# power.net
KiCad netlist of a schematic drawn in Altium Designer
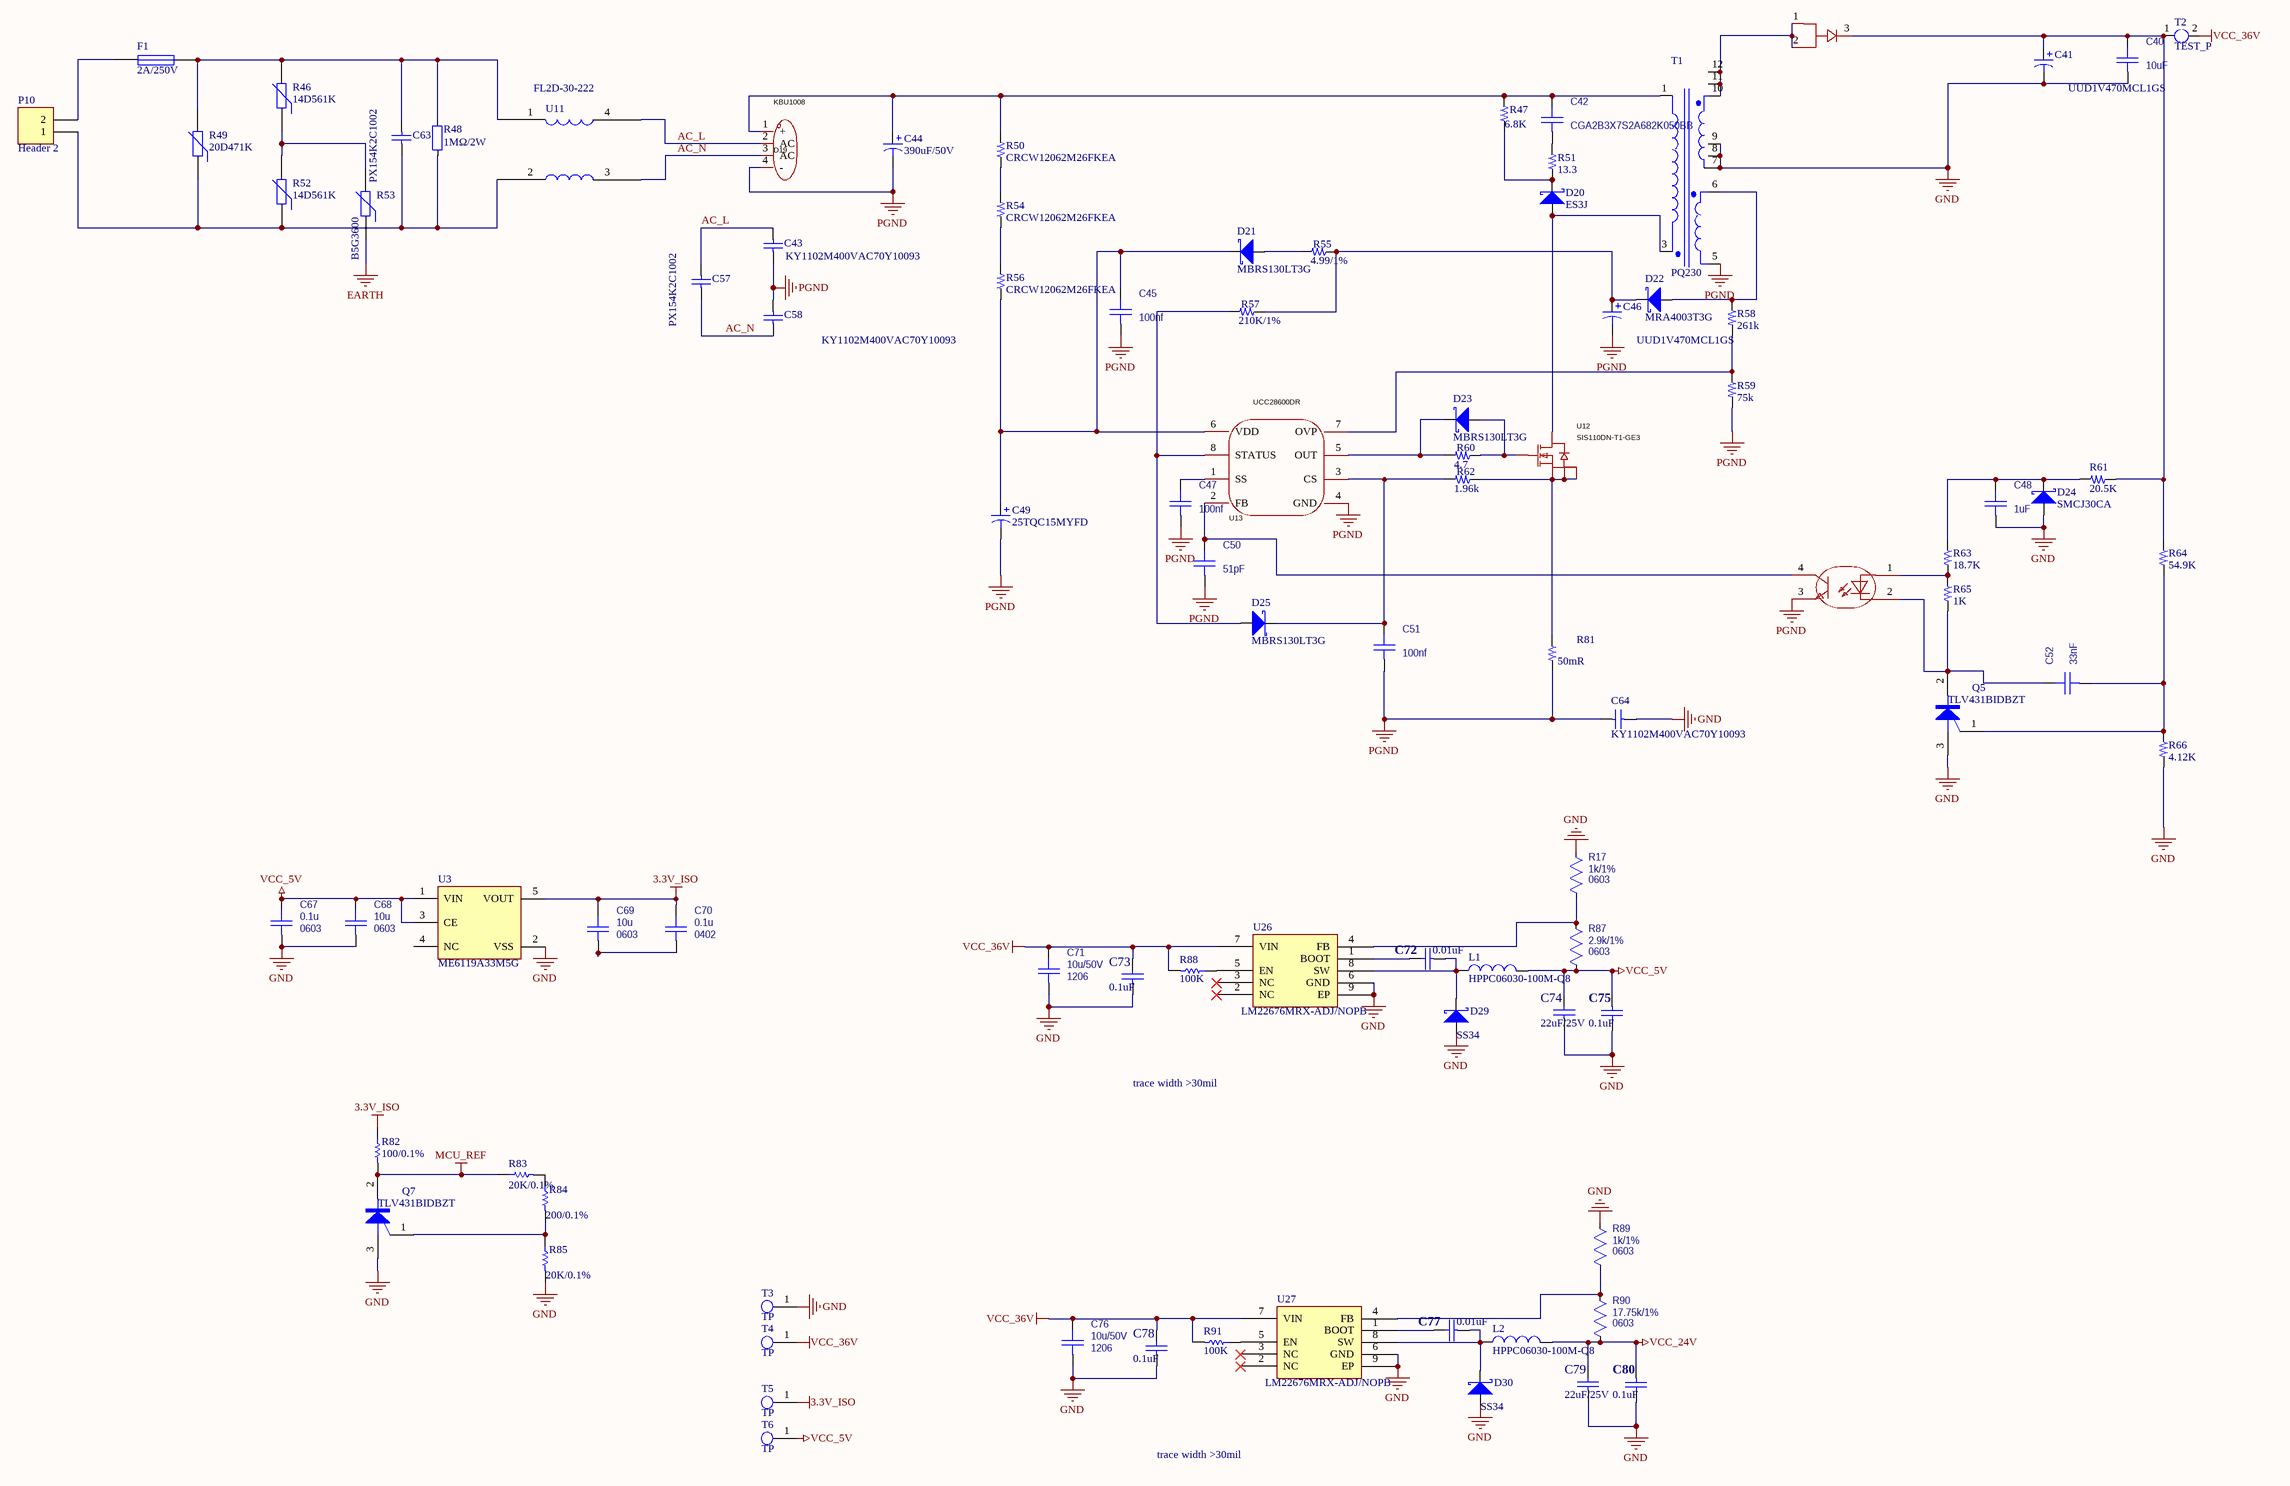
[diagram p0: power.SchDoc]

(export (version "E")
  (design (tool "Eeschema 10.0.6"))
  (components
    (comp (ref "C40")
      (value "Capacitor_0603")
      (footprint "0603c")
      (description "Capacitor, MLCC")
      (fields
        (field (name "MANUFACTURER") "Murata Electronics")
        (field (name "PARTNUMBER") "GRM188R61A106KE69D")
        (field (name "PACKAGE") "10uF")
      )
      (libsource (lib "Karl") (part "Capacitor_0603"))
    )
    (comp (ref "C41")
      (value "UUD1V470MCL1GS")
      (footprint "Φ10×10")
      (description "Polarized Capacitor (Radial)")
      (fields (field (name "PUBLISHER") "Altium Limited"))
      (libsource (lib "Miscellaneous Devices") (part "Cap Pol1"))
    )
    (comp (ref "C42")
      (value "Capacitor_0603")
      (footprint "0402c")
      (description "Capacitor, MLCC")
      (fields
        (field (name "MANUFACTURER") "Murata Electronics")
        (field (name "PARTNUMBER") "GRM188R61A106KE69D")
        (field (name "PACKAGE") "CGA2B3X7S2A682K050BB")
      )
      (libsource (lib "Karl") (part "Capacitor_0603"))
    )
    (comp (ref "C43")
      (value "KY1102M400VAC70Y10093")
      (footprint "CAP-TH_L7.5-W4.5-P10.00-D0.6")
      (description "Capacitor")
      (fields (field (name "PUBLISHER") "Altium Limited"))
      (libsource (lib "Miscellaneous Devices") (part "Cap"))
    )
    (comp (ref "C44")
      (value "390uF/50V")
      (footprint "LGX2H391MELC50")
      (description "Polarized Capacitor (Radial)")
      (fields (field (name "PUBLISHER") "Altium Limited"))
      (libsource (lib "Miscellaneous Devices") (part "Cap Pol1"))
    )
    (comp (ref "C45")
      (value "Capacitor_0603")
      (footprint "0603c")
      (description "Capacitor, MLCC")
      (fields
        (field (name "MANUFACTURER") "Murata Electronics")
        (field (name "PARTNUMBER") "GRM188R61A106KE69D")
        (field (name "PACKAGE") "100nf")
      )
      (libsource (lib "Karl") (part "Capacitor_0603"))
    )
    (comp (ref "C46")
      (value "UUD1V470MCL1GS")
      (footprint "Φ10×10")
      (description "Polarized Capacitor (Radial)")
      (fields (field (name "PUBLISHER") "Altium Limited"))
      (libsource (lib "Miscellaneous Devices") (part "Cap Pol1"))
    )
    (comp (ref "C47")
      (value "Capacitor_0603")
      (footprint "0603c")
      (description "Capacitor, MLCC")
      (fields
        (field (name "MANUFACTURER") "Murata Electronics")
        (field (name "PARTNUMBER") "GRM188R61A106KE69D")
        (field (name "PACKAGE") "100nf")
      )
      (libsource (lib "Karl") (part "Capacitor_0603"))
    )
    (comp (ref "C48")
      (value "Capacitor_0603")
      (footprint "0402c")
      (description "Capacitor, MLCC")
      (fields
        (field (name "MANUFACTURER") "Murata Electronics")
        (field (name "PARTNUMBER") "GRM188R61A106KE69D")
        (field (name "PACKAGE") "1uF")
      )
      (libsource (lib "Karl") (part "Capacitor_0603"))
    )
    (comp (ref "C49")
      (value "25TQC15MYFD")
      (footprint "7343")
      (description "Polarized Capacitor (Radial)")
      (fields (field (name "PUBLISHER") "Altium Limited"))
      (libsource (lib "Miscellaneous Devices") (part "Cap Pol1"))
    )
    (comp (ref "C50")
      (value "Capacitor_0603")
      (footprint "0603c")
      (description "Capacitor, MLCC")
      (fields
        (field (name "MANUFACTURER") "Murata Electronics")
        (field (name "PARTNUMBER") "GRM188R61A106KE69D")
        (field (name "PACKAGE") "51pF")
      )
      (libsource (lib "Karl") (part "Capacitor_0603"))
    )
    (comp (ref "C51")
      (value "Capacitor_0603")
      (footprint "0603c")
      (description "Capacitor, MLCC")
      (fields
        (field (name "MANUFACTURER") "Murata Electronics")
        (field (name "PARTNUMBER") "GRM188R61A106KE69D")
        (field (name "PACKAGE") "100nf")
      )
      (libsource (lib "Karl") (part "Capacitor_0603"))
    )
    (comp (ref "C52")
      (value "Capacitor_0603")
      (footprint "0603c")
      (description "Capacitor, MLCC")
      (fields
        (field (name "MANUFACTURER") "Murata Electronics")
        (field (name "PARTNUMBER") "GRM188R61A106KE69D")
        (field (name "PACKAGE") "33nF")
      )
      (libsource (lib "Karl") (part "Capacitor_0603"))
    )
    (comp (ref "C57")
      (value "PX154K2C1002")
      (footprint "CAP-TH_L13.0-W6.0-P10.00-D0.6")
      (description "Capacitor")
      (fields (field (name "PUBLISHER") "Altium Limited"))
      (libsource (lib "Miscellaneous Devices") (part "Cap"))
    )
    (comp (ref "C58")
      (value "KY1102M400VAC70Y10093")
      (footprint "CAP-TH_L7.5-W4.5-P10.00-D0.6")
      (description "Capacitor")
      (fields (field (name "PUBLISHER") "Altium Limited"))
      (libsource (lib "Miscellaneous Devices") (part "Cap"))
    )
    (comp (ref "C63")
      (value "PX154K2C1002")
      (footprint "CAP-TH_L13.0-W6.0-P10.00-D0.6")
      (description "Capacitor")
      (fields (field (name "PUBLISHER") "Altium Limited"))
      (libsource (lib "Miscellaneous Devices") (part "Cap"))
    )
    (comp (ref "C64")
      (value "KY1102M400VAC70Y10093")
      (footprint "CAP-TH_L7.5-W4.5-P10.00-D0.6")
      (description "Capacitor")
      (fields (field (name "PUBLISHER") "Altium Limited"))
      (libsource (lib "Miscellaneous Devices") (part "Cap"))
    )
    (comp (ref "C67")
      (value "0.1u")
      (footprint "CAPC1608X092N_0603")
      (description "Capacitor, MLCC")
      (fields
        (field (name "MANUFACTURER") "KEMET")
        (field (name "PARTNUMBER") "C0603C104M5RACTU")
        (field (name "PACKAGE") "0603")
      )
      (libsource (lib "Karl") (part "Capacitor_0603"))
    )
    (comp (ref "C68")
      (value "10u")
      (footprint "CAPC1608X092N_0603")
      (description "Capacitor, MLCC")
      (fields
        (field (name "MANUFACTURER") "Murata Electronics")
        (field (name "PARTNUMBER") "GRM188R61A106KE69D")
        (field (name "PACKAGE") "0603")
      )
      (libsource (lib "Karl") (part "Capacitor_0603"))
    )
    (comp (ref "C69")
      (value "10u")
      (footprint "CAPC1608X092N_0603")
      (description "Capacitor, MLCC")
      (fields
        (field (name "MANUFACTURER") "Murata Electronics")
        (field (name "PARTNUMBER") "GRM188R61A106KE69D")
        (field (name "PACKAGE") "0603")
      )
      (libsource (lib "Karl") (part "Capacitor_0603"))
    )
    (comp (ref "C70")
      (value "0.1u")
      (footprint "CAPC1005X056N_0402")
      (description "Capacitor, MLCC")
      (fields
        (field (name "MANUFACTURER") "Murata Electronics")
        (field (name "PARTNUMBER") "GRM155R71C104KA88J")
        (field (name "PACKAGE") "0402")
      )
      (libsource (lib "Karl") (part "Capacitor_0402"))
    )
    (comp (ref "C71")
      (value "10u/50V")
      (footprint "1206C")
      (fields
        (field (name "PARTNUMBER") "C1206C106M3PACTU")
        (field (name "TOLERANCE") "[tol]")
        (field (name "PACKAGE") "1206")
        (field (name "Comment") "Capacitor_1206")
      )
      (libsource (lib "Karl") (part "Capacitor_1206"))
    )
    (comp (ref "C72") (value "0.01uF") (footprint "0603C") (libsource (lib "*") (part "CAP")))
    (comp (ref "C73") (value "0.1uF") (footprint "0603C") (libsource (lib "*") (part "CAP")))
    (comp (ref "C74") (value "22uF/25V") (footprint "1206C") (libsource (lib "*") (part "CAP")))
    (comp (ref "C75") (value "0.1uF") (footprint "0603C") (libsource (lib "*") (part "CAP")))
    (comp (ref "C76")
      (value "10u/50V")
      (footprint "1206C")
      (fields
        (field (name "PARTNUMBER") "C1206C106M3PACTU")
        (field (name "TOLERANCE") "[tol]")
        (field (name "PACKAGE") "1206")
        (field (name "Comment") "Capacitor_1206")
      )
      (libsource (lib "Karl") (part "Capacitor_1206"))
    )
    (comp (ref "C77") (value "0.01uF") (footprint "0603C") (libsource (lib "*") (part "CAP")))
    (comp (ref "C78") (value "0.1uF") (footprint "0603C") (libsource (lib "*") (part "CAP")))
    (comp (ref "C79") (value "22uF/25V") (footprint "1206C") (libsource (lib "*") (part "CAP")))
    (comp (ref "C80") (value "0.1uF") (footprint "0603C") (libsource (lib "*") (part "CAP")))
    (comp (ref "D18")
      (value "SVT12100VB_R2_00001")
      (footprint "TO-277B_3P-L6.1-W4.3-LS7.0-BR")
      (fields (field (name "MANUFACTURER") "PANJIT(强茂)"))
      (libsource (lib "altium-import") (part "root_2_SVT12100VB_R2_00001_"))
    )
    (comp (ref "D19")
      (value "KBU1008")
      (footprint "KBU_4P-L23.2-W6.8-P5.10")
      (fields (field (name "MANUFACTURER") "YANGJIE(扬杰)"))
      (libsource (lib "altium-import") (part "root_0_KBU1008_"))
    )
    (comp (ref "D20")
      (value "ES3J")
      (footprint "SMC")
      (description "Schottky Diode")
      (libsource (lib "*") (part "DIODE S"))
    )
    (comp (ref "D21")
      (value "MBRS130LT3G")
      (footprint "SMB")
      (description "Schottky Diode")
      (libsource (lib "*") (part "DIODE S"))
    )
    (comp (ref "D22")
      (value "MRA4003T3G")
      (footprint "SMA")
      (description "Schottky Diode")
      (libsource (lib "*") (part "DIODE S"))
    )
    (comp (ref "D23")
      (value "MBRS130LT3G")
      (footprint "SMB")
      (description "Schottky Diode")
      (libsource (lib "*") (part "DIODE S"))
    )
    (comp (ref "D24")
      (value "SMCJ30CA")
      (footprint "SMC")
      (description "Schottky Diode")
      (libsource (lib "*") (part "DIODE S"))
    )
    (comp (ref "D25")
      (value "MBRS130LT3G")
      (footprint "SMB")
      (description "Schottky Diode")
      (libsource (lib "*") (part "DIODE S"))
    )
    (comp (ref "D29") (value "SS34") (footprint "SMA") (libsource (lib "*") (part "DIODE S")))
    (comp (ref "D30") (value "SS34") (footprint "SMA") (libsource (lib "*") (part "DIODE S")))
    (comp (ref "F1")
      (value "2A/250V")
      (footprint "可视开关电源保险丝座")
      (description "Fuse")
      (fields (field (name "PUBLISHER") "Altium Limited"))
      (libsource (lib "Miscellaneous Devices") (part "Fuse 1"))
    )
    (comp (ref "L1")
      (value "HPPC06030-100M-Q8")
      (footprint "IND-SMD-L7.3-W6")
      (fields (field (name "PARTNUMBER") "1276AS-H-100M=P2"))
      (libsource (lib "Bogen") (part "1276AS-H-100M=P2"))
    )
    (comp (ref "L2")
      (value "HPPC06030-100M-Q8")
      (footprint "IND-SMD-L7.3-W6")
      (fields (field (name "PARTNUMBER") "1276AS-H-100M=P2"))
      (libsource (lib "Bogen") (part "1276AS-H-100M=P2"))
    )
    (comp (ref "P10")
      (value "Header 2")
      (footprint "HDR1X2")
      (description "Header, 2-Pin")
      (fields (field (name "PUBLISHER") "Altium Limited"))
      (libsource (lib "Miscellaneous Connectors") (part "Header 2"))
    )
    (comp (ref "Q5")
      (value "TLV431BIDBZT")
      (footprint "SOT23-3")
      (description "Programmable Unijunction Transistor")
      (fields (field (name "PUBLISHER") "Altium Limited"))
      (libsource (lib "Miscellaneous Devices") (part "PUT"))
    )
    (comp (ref "Q7")
      (value "TLV431BIDBZT")
      (footprint "SOT23-3")
      (description "Programmable Unijunction Transistor")
      (fields (field (name "PUBLISHER") "Altium Limited"))
      (libsource (lib "Miscellaneous Devices") (part "PUT"))
    )
    (comp (ref "R17")
      (value "1k/1%")
      (footprint "0603R")
      (fields
        (field (name "PARTNUMBER") "RC0603FR-1075KL")
        (field (name "TOLERANCE") "tol")
        (field (name "PACKAGE") "0603")
        (field (name "Comment") "Resistor_0603")
      )
      (libsource (lib "Karl") (part "Resistor_0603"))
    )
    (comp (ref "R46")
      (value "14D561K")
      (footprint "14D561K")
      (description "Varistor (Voltage-Sensitive Resistor)")
      (fields (field (name "PUBLISHER") "Altium Limited"))
      (libsource (lib "Miscellaneous Devices") (part "Res Varistor"))
    )
    (comp (ref "R47")
      (value "6.8K")
      (footprint "0603R")
      (description "R")
      (libsource (lib "JRJ_1") (part "R"))
    )
    (comp (ref "R48") (value "1MΩ/2W") (footprint "5x15.5") (libsource (lib "RC_M_D_00") (part "RES0603")))
    (comp (ref "R49")
      (value "20D471K")
      (footprint "20D471K")
      (description "Varistor (Voltage-Sensitive Resistor)")
      (fields (field (name "PUBLISHER") "Altium Limited"))
      (libsource (lib "Miscellaneous Devices") (part "Res Varistor"))
    )
    (comp (ref "R50")
      (value "CRCW12062M26FKEA")
      (footprint "1206R")
      (description "R")
      (libsource (lib "JRJ_1") (part "R"))
    )
    (comp (ref "R51")
      (value "13.3")
      (footprint "0603R")
      (description "R")
      (libsource (lib "JRJ_1") (part "R"))
    )
    (comp (ref "R52")
      (value "14D561K")
      (footprint "14D561K")
      (description "Varistor (Voltage-Sensitive Resistor)")
      (fields (field (name "PUBLISHER") "Altium Limited"))
      (libsource (lib "Miscellaneous Devices") (part "Res Varistor"))
    )
    (comp (ref "R53")
      (value "B5G3600")
      (footprint "B5G3600")
      (description "Varistor (Voltage-Sensitive Resistor)")
      (fields (field (name "PUBLISHER") "Altium Limited"))
      (libsource (lib "Miscellaneous Devices") (part "Res Varistor"))
    )
    (comp (ref "R54")
      (value "CRCW12062M26FKEA")
      (footprint "1206R")
      (description "R")
      (libsource (lib "JRJ_1") (part "R"))
    )
    (comp (ref "R55")
      (value "4.99/1%")
      (footprint "0603R")
      (description "R")
      (libsource (lib "JRJ_1") (part "R"))
    )
    (comp (ref "R56")
      (value "CRCW12062M26FKEA")
      (footprint "1206R")
      (description "R")
      (libsource (lib "JRJ_1") (part "R"))
    )
    (comp (ref "R57")
      (value "210K/1%")
      (footprint "0603R")
      (description "R")
      (libsource (lib "JRJ_1") (part "R"))
    )
    (comp (ref "R58")
      (value "261k")
      (footprint "0603R")
      (description "R")
      (libsource (lib "JRJ_1") (part "R"))
    )
    (comp (ref "R59")
      (value "75k")
      (footprint "0603R")
      (description "R")
      (libsource (lib "JRJ_1") (part "R"))
    )
    (comp (ref "R60")
      (value "4.7")
      (footprint "0603R")
      (description "R")
      (libsource (lib "JRJ_1") (part "R"))
    )
    (comp (ref "R61")
      (value "20.5K")
      (footprint "0603R")
      (description "R")
      (libsource (lib "JRJ_1") (part "R"))
    )
    (comp (ref "R62")
      (value "1.96k")
      (footprint "0603R")
      (description "R")
      (libsource (lib "JRJ_1") (part "R"))
    )
    (comp (ref "R63")
      (value "18.7K")
      (footprint "0603R")
      (description "R")
      (libsource (lib "JRJ_1") (part "R"))
    )
    (comp (ref "R64")
      (value "54.9K")
      (footprint "0603R")
      (description "R")
      (libsource (lib "JRJ_1") (part "R"))
    )
    (comp (ref "R65") (value "1K") (footprint "0603R") (description "R") (libsource (lib "JRJ_1") (part "R")))
    (comp (ref "R66")
      (value "4.12K")
      (footprint "0603R")
      (description "R")
      (libsource (lib "JRJ_1") (part "R"))
    )
    (comp (ref "R81")
      (value "50mR")
      (footprint "2512R")
      (description "R")
      (libsource (lib "JRJ_1") (part "R"))
    )
    (comp (ref "R82")
      (value "100/0.1%")
      (footprint "0603R")
      (description "Resistor")
      (fields (field (name "PUBLISHER") "Altium Limited"))
      (libsource (lib "Miscellaneous Devices") (part "Res1"))
    )
    (comp (ref "R83")
      (value "20K/0.1%")
      (footprint "0603R")
      (description "Resistor")
      (fields (field (name "Comment") "1K/0.1%") (field (name "PUBLISHER") "Altium Limited"))
      (libsource (lib "Miscellaneous Devices") (part "Res1"))
    )
    (comp (ref "R84")
      (value "200/0.1%")
      (footprint "0603R")
      (description "Resistor")
      (fields (field (name "Comment") "1K/0.1%") (field (name "PUBLISHER") "Altium Limited"))
      (libsource (lib "Miscellaneous Devices") (part "Res1"))
    )
    (comp (ref "R85")
      (value "20K/0.1%")
      (footprint "0603R")
      (description "Resistor")
      (fields (field (name "Comment") "1K/0.1%") (field (name "PUBLISHER") "Altium Limited"))
      (libsource (lib "Miscellaneous Devices") (part "Res1"))
    )
    (comp (ref "R87")
      (value "2.9k/1%")
      (footprint "0603R")
      (fields
        (field (name "PARTNUMBER") "RC0603FR-1075KL")
        (field (name "TOLERANCE") "tol")
        (field (name "PACKAGE") "0603")
        (field (name "Comment") "Resistor_0603")
      )
      (libsource (lib "Karl") (part "Resistor_0603"))
    )
    (comp (ref "R88")
      (value "100K")
      (footprint "0603R")
      (fields (field (name "PUBLISHER") "Altium Limited"))
      (libsource (lib "Miscellaneous Devices") (part "Res1"))
    )
    (comp (ref "R89")
      (value "1k/1%")
      (footprint "0603R")
      (fields
        (field (name "PARTNUMBER") "RC0603FR-1075KL")
        (field (name "TOLERANCE") "tol")
        (field (name "PACKAGE") "0603")
        (field (name "Comment") "Resistor_0603")
      )
      (libsource (lib "Karl") (part "Resistor_0603"))
    )
    (comp (ref "R90")
      (value "17.75k/1%")
      (footprint "0603R")
      (fields
        (field (name "PARTNUMBER") "RC0603FR-1075KL")
        (field (name "TOLERANCE") "tol")
        (field (name "PACKAGE") "0603")
        (field (name "Comment") "Resistor_0603")
      )
      (libsource (lib "Karl") (part "Resistor_0603"))
    )
    (comp (ref "R91")
      (value "100K")
      (footprint "0603R")
      (fields (field (name "PUBLISHER") "Altium Limited"))
      (libsource (lib "Miscellaneous Devices") (part "Res1"))
    )
    (comp (ref "T1") (value "PQ230") (footprint "pq3230") (libsource (lib "Schlib_20110825") (part "PQ230")))
    (comp (ref "T2")
      (value "TEST_P")
      (footprint "TEST_P")
      (libsource (lib "Schlib_20110825") (part "TEST_P"))
    )
    (comp (ref "T3") (value "TP") (footprint "TPD") (libsource (lib "Schlib_20110825") (part "TP")))
    (comp (ref "T4") (value "TP") (footprint "TPD") (libsource (lib "Schlib_20110825") (part "TP")))
    (comp (ref "T5") (value "TP") (footprint "TPD") (libsource (lib "Schlib_20110825") (part "TP")))
    (comp (ref "T6") (value "TP") (footprint "TPD") (libsource (lib "Schlib_20110825") (part "TP")))
    (comp (ref "U3")
      (value "ME6119A33M5G")
      (footprint "MCRN-SOT23-5_V")
      (libsource (lib "Bogen") (part "ME6119C50M5G"))
    )
    (comp (ref "U11")
      (value "FL2D-30-222")
      (footprint "TY-100P")
      (description "PCB mounting filters")
      (libsource (lib "power") (part "TY-100P"))
    )
    (comp (ref "U12")
      (value "SIS110DN-T1-GE3")
      (footprint "DFN-8_L3.3-W3.3-P0.65-BL-2")
      (fields (field (name "MANUFACTURER") "VISHAY(威世)"))
      (libsource (lib "altium-import") (part "root_0_SIS110DN-T1-GE3_"))
    )
    (comp (ref "U13")
      (value "UCC28600DR")
      (footprint "so-8")
      (fields (field (name "MANUFACTURER") "TI(德州仪器)"))
      (libsource (lib "UCC28600DR1_UCC28600DR") (part "UCC28600DR"))
    )
    (comp (ref "U14")
      (value "TCMT1107")
      (footprint "sop4")
      (fields (field (name "MANUFACTURER") "VISHAY(威世)"))
      (libsource (lib "altium-import") (part "root_0_mirrored_TCMT1107_"))
    )
    (comp (ref "U26")
      (value "LM22676MRX-ADJ/NOPB")
      (footprint "SOP127P600X168_HS-8N")
      (libsource (lib "Schlib1") (part "LM22676MR-5.0"))
    )
    (comp (ref "U27")
      (value "LM22676MRX-ADJ/NOPB")
      (footprint "SOP127P600X168_HS-8N")
      (libsource (lib "Schlib1") (part "LM22676MR-5.0"))
    )
  )
  (nets
    (net (code "1") (name "/AC_L") (class "Default")
      (node (ref "C43") (pin "2") (pinfunction "2_2") (pintype "passive"))
      (node (ref "C57") (pin "2") (pinfunction "2_2") (pintype "passive"))
      (node (ref "D19") (pin "2") (pinfunction "AC_2") (pintype "passive"))
      (node (ref "U11") (pin "4") (pinfunction "L_4") (pintype "passive"))
    )
    (net (code "2") (name "/AC_N") (class "Default")
      (node (ref "C57") (pin "1") (pinfunction "1_1") (pintype "passive"))
      (node (ref "C58") (pin "1") (pinfunction "1_1") (pintype "passive"))
      (node (ref "D19") (pin "3") (pinfunction "AC_3") (pintype "passive"))
      (node (ref "U11") (pin "3") (pintype "passive"))
    )
    (net (code "3") (name "3.3V_ISO") (class "Default")
      (node (ref "C69") (pin "1") (pinfunction "1_1") (pintype "passive"))
      (node (ref "C70") (pin "1") (pinfunction "1_1") (pintype "passive"))
      (node (ref "R82") (pin "1") (pinfunction "1_1") (pintype "passive"))
      (node (ref "T5") (pin "1") (pintype "passive"))
      (node (ref "U3") (pin "5") (pinfunction "VOUT_5") (pintype "passive"))
    )
    (net (code "4") (name "EARTH") (class "Default")
      (node (ref "R53") (pin "1") (pinfunction "1_1") (pintype "passive"))
    )
    (net (code "5") (name "GND") (class "Default")
      (node (ref "C40") (pin "2") (pinfunction "2_2") (pintype "passive"))
      (node (ref "C41") (pin "2") (pinfunction "2_2") (pintype "passive"))
      (node (ref "C48") (pin "2") (pinfunction "2_2") (pintype "passive"))
      (node (ref "C64") (pin "1") (pinfunction "1_1") (pintype "passive"))
      (node (ref "C67") (pin "2") (pinfunction "2_2") (pintype "passive"))
      (node (ref "C68") (pin "2") (pinfunction "2_2") (pintype "passive"))
      (node (ref "C71") (pin "2") (pinfunction "2_2") (pintype "passive"))
      (node (ref "C73") (pin "1") (pinfunction "1_1") (pintype "passive"))
      (node (ref "C74") (pin "1") (pinfunction "1_1") (pintype "passive"))
      (node (ref "C75") (pin "2") (pinfunction "2_2") (pintype "passive"))
      (node (ref "C76") (pin "2") (pinfunction "2_2") (pintype "passive"))
      (node (ref "C78") (pin "1") (pinfunction "1_1") (pintype "passive"))
      (node (ref "C79") (pin "1") (pinfunction "1_1") (pintype "passive"))
      (node (ref "C80") (pin "2") (pinfunction "2_2") (pintype "passive"))
      (node (ref "D24") (pin "1") (pinfunction "A_1") (pintype "passive"))
      (node (ref "D29") (pin "1") (pinfunction "A_1") (pintype "passive"))
      (node (ref "D30") (pin "1") (pinfunction "A_1") (pintype "passive"))
      (node (ref "Q5") (pin "3") (pinfunction "A_3") (pintype "passive"))
      (node (ref "Q7") (pin "3") (pinfunction "A_3") (pintype "passive"))
      (node (ref "R17") (pin "2") (pinfunction "2_2") (pintype "passive"))
      (node (ref "R66") (pin "2") (pintype "passive"))
      (node (ref "R85") (pin "2") (pinfunction "2_2") (pintype "passive"))
      (node (ref "R89") (pin "2") (pinfunction "2_2") (pintype "passive"))
      (node (ref "T1") (pin "7") (pinfunction "Pri-_7") (pintype "passive"))
      (node (ref "T1") (pin "8") (pinfunction "Pri-_8") (pintype "passive"))
      (node (ref "T1") (pin "9") (pinfunction "Pri-_9") (pintype "passive"))
      (node (ref "T3") (pin "1") (pintype "passive"))
      (node (ref "U26") (pin "6") (pinfunction "GND_6") (pintype "passive"))
      (node (ref "U26") (pin "9") (pinfunction "EP_9") (pintype "passive"))
      (node (ref "U27") (pin "6") (pinfunction "GND_6") (pintype "passive"))
      (node (ref "U27") (pin "9") (pinfunction "EP_9") (pintype "passive"))
      (node (ref "U3") (pin "2") (pinfunction "VSS_2") (pintype "passive"))
    )
    (net (code "6") (name "MCU_REF") (class "Default")
      (node (ref "Q7") (pin "2") (pinfunction "K_2") (pintype "passive"))
      (node (ref "R82") (pin "2") (pinfunction "2_2") (pintype "passive"))
      (node (ref "R83") (pin "1") (pinfunction "1_1") (pintype "passive"))
    )
    (net (code "7") (name "Net-(C40-Pad1)") (class "Default")
      (node (ref "C40") (pin "1") (pinfunction "1_1") (pintype "passive"))
      (node (ref "C41") (pin "1") (pinfunction "1_1") (pintype "passive"))
      (node (ref "D18") (pin "3") (pinfunction "3_3") (pintype "passive"))
      (node (ref "R61") (pin "1") (pintype "passive"))
      (node (ref "R64") (pin "1") (pintype "passive"))
      (node (ref "T2") (pin "1") (pinfunction "1_1") (pintype "passive"))
    )
    (net (code "8") (name "Net-(C42-Pad2)") (class "Default")
      (node (ref "C42") (pin "2") (pinfunction "2_2") (pintype "passive"))
      (node (ref "R51") (pin "2") (pintype "passive"))
    )
    (net (code "9") (name "Net-(C63-Pad1)") (class "Default")
      (node (ref "C63") (pin "1") (pinfunction "1_1") (pintype "passive"))
      (node (ref "P10") (pin "1") (pinfunction "1_1") (pintype "passive"))
      (node (ref "R48") (pin "2") (pinfunction "2_2") (pintype "passive"))
      (node (ref "R49") (pin "1") (pinfunction "1_1") (pintype "passive"))
      (node (ref "R52") (pin "1") (pinfunction "1_1") (pintype "passive"))
      (node (ref "U11") (pin "2") (pinfunction "L_2") (pintype "passive"))
    )
    (net (code "10") (name "Net-(C63-Pad2)") (class "Default")
      (node (ref "C63") (pin "2") (pinfunction "2_2") (pintype "passive"))
      (node (ref "F1") (pin "2") (pinfunction "2_2") (pintype "passive"))
      (node (ref "R46") (pin "2") (pinfunction "2_2") (pintype "passive"))
      (node (ref "R48") (pin "1") (pinfunction "1_1") (pintype "passive"))
      (node (ref "R49") (pin "2") (pinfunction "2_2") (pintype "passive"))
      (node (ref "U11") (pin "1") (pinfunction "L_1") (pintype "passive"))
    )
    (net (code "11") (name "Net-(C69-Pad2)") (class "Default")
      (node (ref "C69") (pin "2") (pinfunction "2_2") (pintype "passive"))
      (node (ref "C70") (pin "2") (pinfunction "2_2") (pintype "passive"))
    )
    (net (code "12") (name "Net-(D18-Pad1)") (class "Default")
      (node (ref "D18") (pin "1") (pinfunction "1_1") (pintype "passive"))
      (node (ref "D18") (pin "2") (pinfunction "2_2") (pintype "passive"))
      (node (ref "T1") (pin "10") (pinfunction "Pri+_10") (pintype "passive"))
      (node (ref "T1") (pin "11") (pinfunction "Pri+_11") (pintype "passive"))
      (node (ref "T1") (pin "12") (pinfunction "Pri+_12") (pintype "passive"))
    )
    (net (code "13") (name "Net-(D19-+)") (class "Default")
      (node (ref "C42") (pin "1") (pinfunction "1_1") (pintype "passive"))
      (node (ref "C44") (pin "1") (pinfunction "1_1") (pintype "passive"))
      (node (ref "D19") (pin "1") (pinfunction "+_1") (pintype "passive"))
      (node (ref "R47") (pin "2") (pintype "passive"))
      (node (ref "R50") (pin "2") (pintype "passive"))
      (node (ref "T1") (pin "1") (pinfunction "Pri+_1") (pintype "passive"))
    )
    (net (code "14") (name "Net-(D20-A)") (class "Default")
      (node (ref "D20") (pin "1") (pinfunction "A_1") (pintype "passive"))
      (node (ref "T1") (pin "3") (pinfunction "Pri-_3") (pintype "passive"))
      (node (ref "U12") (pin "5") (pinfunction "D_5") (pintype "passive"))
    )
    (net (code "15") (name "Net-(D20-K)") (class "Default")
      (node (ref "D20") (pin "2") (pinfunction "K_2") (pintype "passive"))
      (node (ref "R47") (pin "1") (pintype "passive"))
      (node (ref "R51") (pin "1") (pintype "passive"))
    )
    (net (code "16") (name "Net-(D21-A)") (class "Default")
      (node (ref "D21") (pin "1") (pinfunction "A_1") (pintype "passive"))
      (node (ref "R55") (pin "2") (pintype "passive"))
    )
    (net (code "17") (name "Net-(D21-K)") (class "Default")
      (node (ref "C45") (pin "1") (pinfunction "1_1") (pintype "passive"))
      (node (ref "C49") (pin "1") (pinfunction "1_1") (pintype "passive"))
      (node (ref "D21") (pin "2") (pinfunction "K_2") (pintype "passive"))
      (node (ref "R56") (pin "1") (pintype "passive"))
      (node (ref "U13") (pin "6") (pinfunction "VDD_6") (pintype "passive"))
    )
    (net (code "18") (name "Net-(D22-A)") (class "Default")
      (node (ref "D22") (pin "1") (pinfunction "A_1") (pintype "passive"))
      (node (ref "R58") (pin "1") (pintype "passive"))
      (node (ref "T1") (pin "6") (pinfunction "Pri-_6") (pintype "passive"))
    )
    (net (code "19") (name "Net-(D22-K)") (class "Default")
      (node (ref "C46") (pin "1") (pinfunction "1_1") (pintype "passive"))
      (node (ref "D22") (pin "2") (pinfunction "K_2") (pintype "passive"))
      (node (ref "R55") (pin "1") (pintype "passive"))
      (node (ref "R57") (pin "1") (pintype "passive"))
    )
    (net (code "20") (name "Net-(D23-A)") (class "Default")
      (node (ref "D23") (pin "1") (pinfunction "A_1") (pintype "passive"))
      (node (ref "R60") (pin "1") (pintype "passive"))
      (node (ref "U12") (pin "4") (pinfunction "G_4") (pintype "passive"))
    )
    (net (code "21") (name "Net-(D23-K)") (class "Default")
      (node (ref "D23") (pin "2") (pinfunction "K_2") (pintype "passive"))
      (node (ref "R60") (pin "2") (pintype "passive"))
      (node (ref "U13") (pin "5") (pinfunction "OUT_5") (pintype "passive"))
    )
    (net (code "22") (name "Net-(D24-K)") (class "Default")
      (node (ref "C48") (pin "1") (pinfunction "1_1") (pintype "passive"))
      (node (ref "D24") (pin "2") (pinfunction "K_2") (pintype "passive"))
      (node (ref "R61") (pin "2") (pintype "passive"))
      (node (ref "R63") (pin "1") (pintype "passive"))
    )
    (net (code "23") (name "Net-(D25-A)") (class "Default")
      (node (ref "D25") (pin "1") (pinfunction "A_1") (pintype "passive"))
      (node (ref "R57") (pin "2") (pintype "passive"))
      (node (ref "U13") (pin "8") (pinfunction "STATUS_8") (pintype "passive"))
    )
    (net (code "24") (name "Net-(D25-K)") (class "Default")
      (node (ref "C51") (pin "1") (pinfunction "1_1") (pintype "passive"))
      (node (ref "D25") (pin "2") (pinfunction "K_2") (pintype "passive"))
      (node (ref "R62") (pin "2") (pintype "passive"))
      (node (ref "U13") (pin "3") (pinfunction "CS_3") (pintype "passive"))
    )
    (net (code "25") (name "Net-(D29-K)") (class "Default")
      (node (ref "C72") (pin "1") (pinfunction "1_1") (pintype "passive"))
      (node (ref "D29") (pin "2") (pinfunction "K_2") (pintype "passive"))
      (node (ref "L1") (pin "1") (pinfunction "1_1") (pintype "passive"))
      (node (ref "U26") (pin "8") (pinfunction "SW_8") (pintype "passive"))
    )
    (net (code "26") (name "Net-(D30-K)") (class "Default")
      (node (ref "C77") (pin "1") (pinfunction "1_1") (pintype "passive"))
      (node (ref "D30") (pin "2") (pinfunction "K_2") (pintype "passive"))
      (node (ref "L2") (pin "1") (pinfunction "1_1") (pintype "passive"))
      (node (ref "U27") (pin "8") (pinfunction "SW_8") (pintype "passive"))
    )
    (net (code "27") (name "Net-(F1-Pad1)") (class "Default")
      (node (ref "F1") (pin "1") (pinfunction "1_1") (pintype "passive"))
      (node (ref "P10") (pin "2") (pinfunction "2_2") (pintype "passive"))
    )
    (net (code "28") (name "Net-(Q5-G)") (class "Default")
      (node (ref "C52") (pin "2") (pinfunction "2_2") (pintype "passive"))
      (node (ref "Q5") (pin "1") (pinfunction "G_1") (pintype "passive"))
      (node (ref "R64") (pin "2") (pintype "passive"))
      (node (ref "R66") (pin "1") (pintype "passive"))
    )
    (net (code "29") (name "Net-(Q5-K)") (class "Default")
      (node (ref "C52") (pin "1") (pinfunction "1_1") (pintype "passive"))
      (node (ref "Q5") (pin "2") (pinfunction "K_2") (pintype "passive"))
      (node (ref "R65") (pin "2") (pintype "passive"))
      (node (ref "U14") (pin "2") (pinfunction "CAT_2") (pintype "passive"))
    )
    (net (code "30") (name "Net-(Q7-G)") (class "Default")
      (node (ref "Q7") (pin "1") (pinfunction "G_1") (pintype "passive"))
      (node (ref "R84") (pin "2") (pinfunction "2_2") (pintype "passive"))
      (node (ref "R85") (pin "1") (pinfunction "1_1") (pintype "passive"))
    )
    (net (code "31") (name "Net-(R46-Pad1)") (class "Default")
      (node (ref "R46") (pin "1") (pinfunction "1_1") (pintype "passive"))
      (node (ref "R52") (pin "2") (pinfunction "2_2") (pintype "passive"))
      (node (ref "R53") (pin "2") (pinfunction "2_2") (pintype "passive"))
    )
    (net (code "32") (name "Net-(R50-Pad1)") (class "Default")
      (node (ref "R50") (pin "1") (pintype "passive"))
      (node (ref "R54") (pin "2") (pintype "passive"))
    )
    (net (code "33") (name "Net-(R54-Pad1)") (class "Default")
      (node (ref "R54") (pin "1") (pintype "passive"))
      (node (ref "R56") (pin "2") (pintype "passive"))
    )
    (net (code "34") (name "Net-(R62-Pad1)") (class "Default")
      (node (ref "R62") (pin "1") (pintype "passive"))
      (node (ref "R81") (pin "1") (pintype "passive"))
      (node (ref "U12") (pin "1") (pinfunction "S_1") (pintype "passive"))
      (node (ref "U12") (pin "2") (pinfunction "S_2") (pintype "passive"))
      (node (ref "U12") (pin "3") (pinfunction "S_3") (pintype "passive"))
    )
    (net (code "35") (name "Net-(R83-Pad2)") (class "Default")
      (node (ref "R83") (pin "2") (pinfunction "2_2") (pintype "passive"))
      (node (ref "R84") (pin "1") (pinfunction "1_1") (pintype "passive"))
    )
    (net (code "36") (name "Net-(U13-FB)") (class "Default")
      (node (ref "C50") (pin "1") (pinfunction "1_1") (pintype "passive"))
      (node (ref "U13") (pin "2") (pinfunction "FB_2") (pintype "passive"))
      (node (ref "U14") (pin "4") (pinfunction "COL_4") (pintype "passive"))
    )
    (net (code "37") (name "Net-(U13-OVP)") (class "Default")
      (node (ref "R58") (pin "2") (pintype "passive"))
      (node (ref "R59") (pin "1") (pintype "passive"))
      (node (ref "U13") (pin "7") (pinfunction "OVP_7") (pintype "passive"))
    )
    (net (code "38") (name "Net-(U13-SS)") (class "Default")
      (node (ref "C47") (pin "1") (pinfunction "1_1") (pintype "passive"))
      (node (ref "U13") (pin "1") (pinfunction "SS_1") (pintype "passive"))
    )
    (net (code "39") (name "Net-(U14-AN)") (class "Default")
      (node (ref "R63") (pin "2") (pintype "passive"))
      (node (ref "R65") (pin "1") (pintype "passive"))
      (node (ref "U14") (pin "1") (pinfunction "AN_1") (pintype "passive"))
    )
    (net (code "40") (name "Net-(U26-BOOT)") (class "Default")
      (node (ref "C72") (pin "2") (pinfunction "2_2") (pintype "passive"))
      (node (ref "U26") (pin "1") (pinfunction "BOOT_1") (pintype "passive"))
    )
    (net (code "41") (name "Net-(U26-EN)") (class "Default")
      (node (ref "R88") (pin "1") (pinfunction "1_1") (pintype "passive"))
      (node (ref "U26") (pin "5") (pinfunction "EN_5") (pintype "passive"))
    )
    (net (code "42") (name "Net-(U26-FB)") (class "Default")
      (node (ref "R17") (pin "1") (pinfunction "1_1") (pintype "passive"))
      (node (ref "R87") (pin "2") (pinfunction "2_2") (pintype "passive"))
      (node (ref "U26") (pin "4") (pinfunction "FB_4") (pintype "passive"))
    )
    (net (code "43") (name "Net-(U27-BOOT)") (class "Default")
      (node (ref "C77") (pin "2") (pinfunction "2_2") (pintype "passive"))
      (node (ref "U27") (pin "1") (pinfunction "BOOT_1") (pintype "passive"))
    )
    (net (code "44") (name "Net-(U27-EN)") (class "Default")
      (node (ref "R91") (pin "1") (pinfunction "1_1") (pintype "passive"))
      (node (ref "U27") (pin "5") (pinfunction "EN_5") (pintype "passive"))
    )
    (net (code "45") (name "Net-(U27-FB)") (class "Default")
      (node (ref "R89") (pin "1") (pinfunction "1_1") (pintype "passive"))
      (node (ref "R90") (pin "2") (pinfunction "2_2") (pintype "passive"))
      (node (ref "U27") (pin "4") (pinfunction "FB_4") (pintype "passive"))
    )
    (net (code "46") (name "PGND") (class "Default")
      (node (ref "C43") (pin "1") (pinfunction "1_1") (pintype "passive"))
      (node (ref "C44") (pin "2") (pinfunction "2_2") (pintype "passive"))
      (node (ref "C45") (pin "2") (pinfunction "2_2") (pintype "passive"))
      (node (ref "C46") (pin "2") (pinfunction "2_2") (pintype "passive"))
      (node (ref "C47") (pin "2") (pinfunction "2_2") (pintype "passive"))
      (node (ref "C49") (pin "2") (pinfunction "2_2") (pintype "passive"))
      (node (ref "C50") (pin "2") (pinfunction "2_2") (pintype "passive"))
      (node (ref "C51") (pin "2") (pinfunction "2_2") (pintype "passive"))
      (node (ref "C58") (pin "2") (pinfunction "2_2") (pintype "passive"))
      (node (ref "C64") (pin "2") (pinfunction "2_2") (pintype "passive"))
      (node (ref "D19") (pin "4") (pinfunction "-_4") (pintype "passive"))
      (node (ref "R59") (pin "2") (pintype "passive"))
      (node (ref "R81") (pin "2") (pintype "passive"))
      (node (ref "T1") (pin "5") (pinfunction "Pri-_5") (pintype "passive"))
      (node (ref "U13") (pin "4") (pinfunction "GND_4") (pintype "passive"))
      (node (ref "U14") (pin "3") (pinfunction "EM_3") (pintype "passive"))
    )
    (net (code "47") (name "VCC_5V") (class "Default")
      (node (ref "C67") (pin "1") (pinfunction "1_1") (pintype "passive"))
      (node (ref "C68") (pin "1") (pinfunction "1_1") (pintype "passive"))
      (node (ref "C74") (pin "2") (pinfunction "2_2") (pintype "passive"))
      (node (ref "C75") (pin "1") (pinfunction "1_1") (pintype "passive"))
      (node (ref "L1") (pin "2") (pinfunction "2_2") (pintype "passive"))
      (node (ref "R87") (pin "1") (pinfunction "1_1") (pintype "passive"))
      (node (ref "T6") (pin "1") (pintype "passive"))
      (node (ref "U3") (pin "1") (pinfunction "VIN_1") (pintype "passive"))
      (node (ref "U3") (pin "3") (pinfunction "CE_3") (pintype "passive"))
    )
    (net (code "48") (name "VCC_24V") (class "Default")
      (node (ref "C79") (pin "2") (pinfunction "2_2") (pintype "passive"))
      (node (ref "C80") (pin "1") (pinfunction "1_1") (pintype "passive"))
      (node (ref "L2") (pin "2") (pinfunction "2_2") (pintype "passive"))
      (node (ref "R90") (pin "1") (pinfunction "1_1") (pintype "passive"))
    )
    (net (code "49") (name "VCC_36V") (class "Default")
      (node (ref "C71") (pin "1") (pinfunction "1_1") (pintype "passive"))
      (node (ref "C73") (pin "2") (pinfunction "2_2") (pintype "passive"))
      (node (ref "C76") (pin "1") (pinfunction "1_1") (pintype "passive"))
      (node (ref "C78") (pin "2") (pinfunction "2_2") (pintype "passive"))
      (node (ref "R88") (pin "2") (pinfunction "2_2") (pintype "passive"))
      (node (ref "R91") (pin "2") (pinfunction "2_2") (pintype "passive"))
      (node (ref "T2") (pin "2") (pinfunction "2_2") (pintype "passive"))
      (node (ref "T4") (pin "1") (pintype "passive"))
      (node (ref "U26") (pin "7") (pinfunction "VIN_7") (pintype "passive"))
      (node (ref "U27") (pin "7") (pinfunction "VIN_7") (pintype "passive"))
    )
    (net (code "50") (name "unconnected-(U3-NC-Pad4)") (class "Default")
      (node (ref "U3") (pin "4") (pinfunction "NC_4") (pintype "passive"))
    )
    (net (code "51") (name "unconnected-(U26-NC-Pad2)") (class "Default")
      (node (ref "U26") (pin "2") (pinfunction "NC_2") (pintype "passive+no_connect"))
    )
    (net (code "52") (name "unconnected-(U26-NC-Pad3)") (class "Default")
      (node (ref "U26") (pin "3") (pinfunction "NC_3") (pintype "passive+no_connect"))
    )
    (net (code "53") (name "unconnected-(U27-NC-Pad2)") (class "Default")
      (node (ref "U27") (pin "2") (pinfunction "NC_2") (pintype "passive+no_connect"))
    )
    (net (code "54") (name "unconnected-(U27-NC-Pad3)") (class "Default")
      (node (ref "U27") (pin "3") (pinfunction "NC_3") (pintype "passive+no_connect"))
    )
  )
)
